# SunS_1v225_Reference.net
KiCad netlist of a schematic drawn in Altium Designer
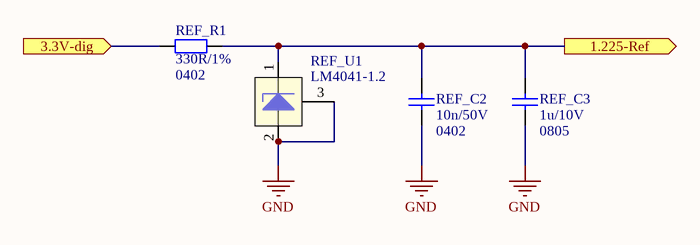
[diagram p0: SunS_1v225_Reference.SchDoc]

(export (version "E")
  (design (tool "Eeschema 10.0.6"))
  (components
    (comp (ref "REF_C2")
      (value "10n/50V")
      (footprint "SMD_Capacitor_0402")
      (description "Ceramic Cap Kemet COTS 10n/50V X7R 0402")
      (fields
        (field (name "MANUFACTURERPARTNUMBER") "C0402T103K5RALTU")
        (field (name "MANUFACTURER") "Kemet")
        (field (name "PACKAGE") "0402")
      )
      (libsource (lib "capacitors") (part "Cer_C0402T103K5RALTU"))
    )
    (comp (ref "REF_C3")
      (value "1u/10V")
      (footprint "SMD_Capacitor_0805")
      (description "Cap")
      (fields (field (name "PACKAGE") "0805"))
      (libsource (lib "capacitors") (part "Cap"))
    )
    (comp (ref "REF_R1")
      (value "330R/1%")
      (footprint "SMD_Resistor_0402")
      (description "1k/1% Vishay CRCW 0402 Resistor. 63mW, 100ppm, 50V.")
      (fields
        (field (name "MANUFACTURER") "Vishay")
        (field (name "MANUFACTURERPARTNUMBER") "CRCW04021K00FKxxxx")
        (field (name "PACKAGE") "0402")
      )
      (libsource (lib "resistors") (part "CRCW04021K00FKxxxx"))
    )
    (comp (ref "REF_U1")
      (value "LM4041-1.2")
      (footprint "SOT23-3")
      (description "Shunt FIXED V-REF, 1.225V")
      (fields
        (field (name "MANUFACTURERPARTNUMBER") "LM4041AIM3X-1.2/NOPB")
        (field (name "MANUFACTURER") "Texas Instruments")
      )
      (libsource (lib "diodes") (part "LM4041AIM3X-1.2/NOPB"))
    )
  )
  (nets
    (net (code "1") (name "/1.225-Ref") (class "Default")
      (node (ref "REF_C2") (pin "1") (pinfunction "1_1") (pintype "passive"))
      (node (ref "REF_C3") (pin "1") (pinfunction "1_1") (pintype "passive"))
      (node (ref "REF_R1") (pin "2") (pinfunction "2_2") (pintype "passive"))
      (node (ref "REF_U1") (pin "1") (pinfunction "K_1") (pintype "passive"))
    )
    (net (code "2") (name "/3.3V-dig") (class "Default")
      (node (ref "REF_R1") (pin "1") (pinfunction "1_1") (pintype "passive"))
    )
    (net (code "3") (name "GND") (class "Default")
      (node (ref "REF_C2") (pin "2") (pinfunction "2_2") (pintype "passive"))
      (node (ref "REF_C3") (pin "2") (pinfunction "2_2") (pintype "passive"))
      (node (ref "REF_U1") (pin "2") (pinfunction "A_2") (pintype "passive"))
      (node (ref "REF_U1") (pin "3") (pinfunction "NC_3") (pintype "passive"))
    )
  )
)
